# TUTUPA_V2_5sch.net
KiCad netlist of a schematic drawn in EAGLE
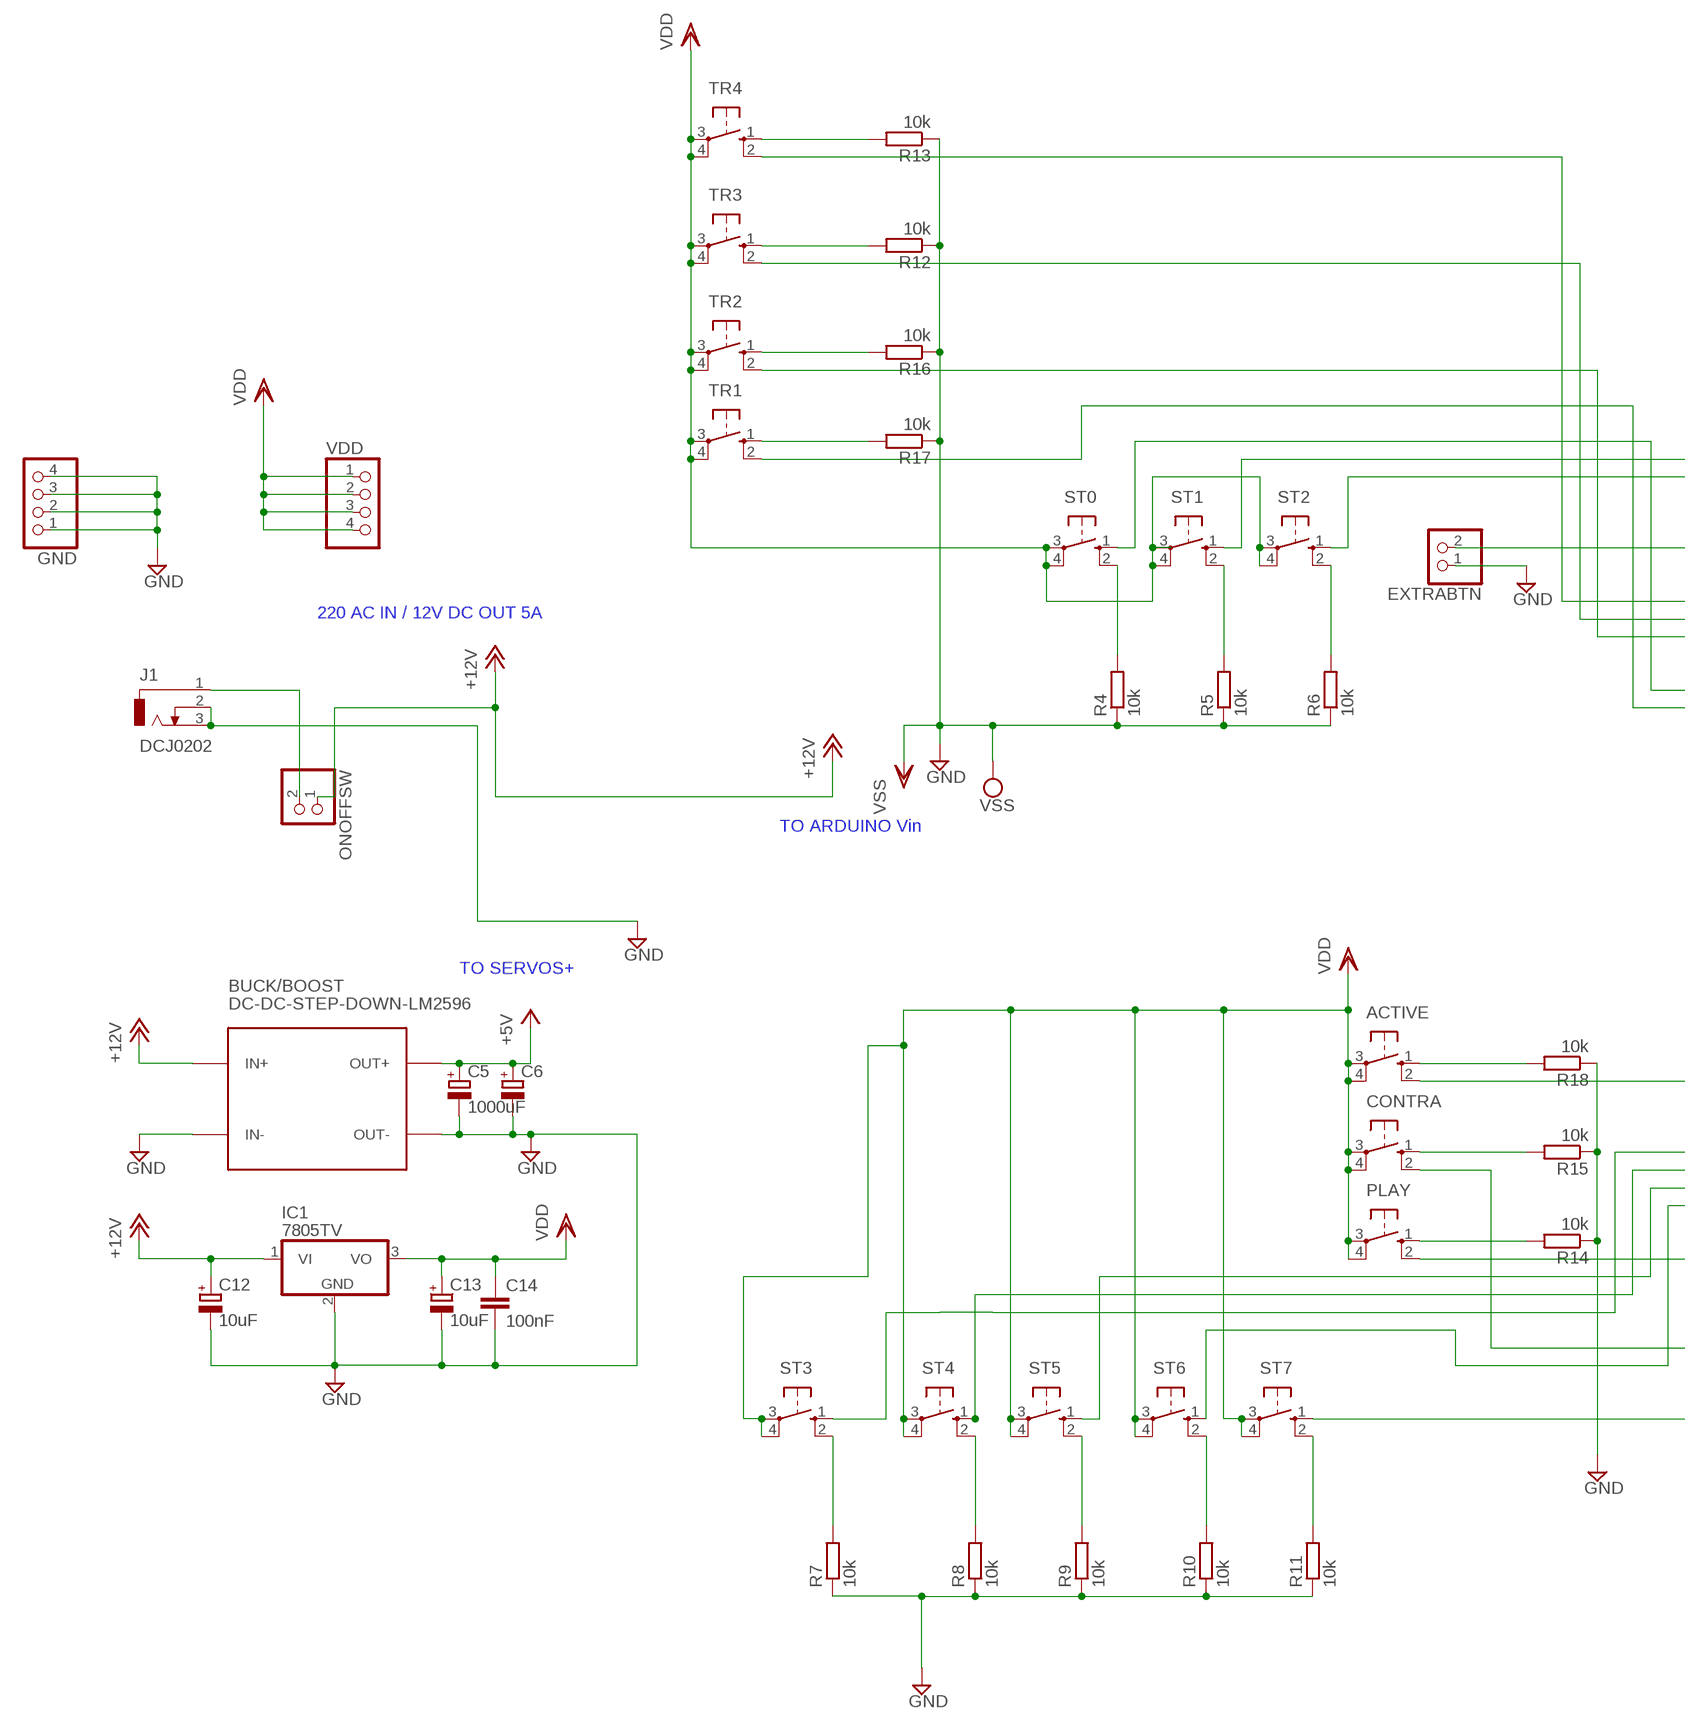
[diagram p0: schematic, sheet 1, part 1 of 2]
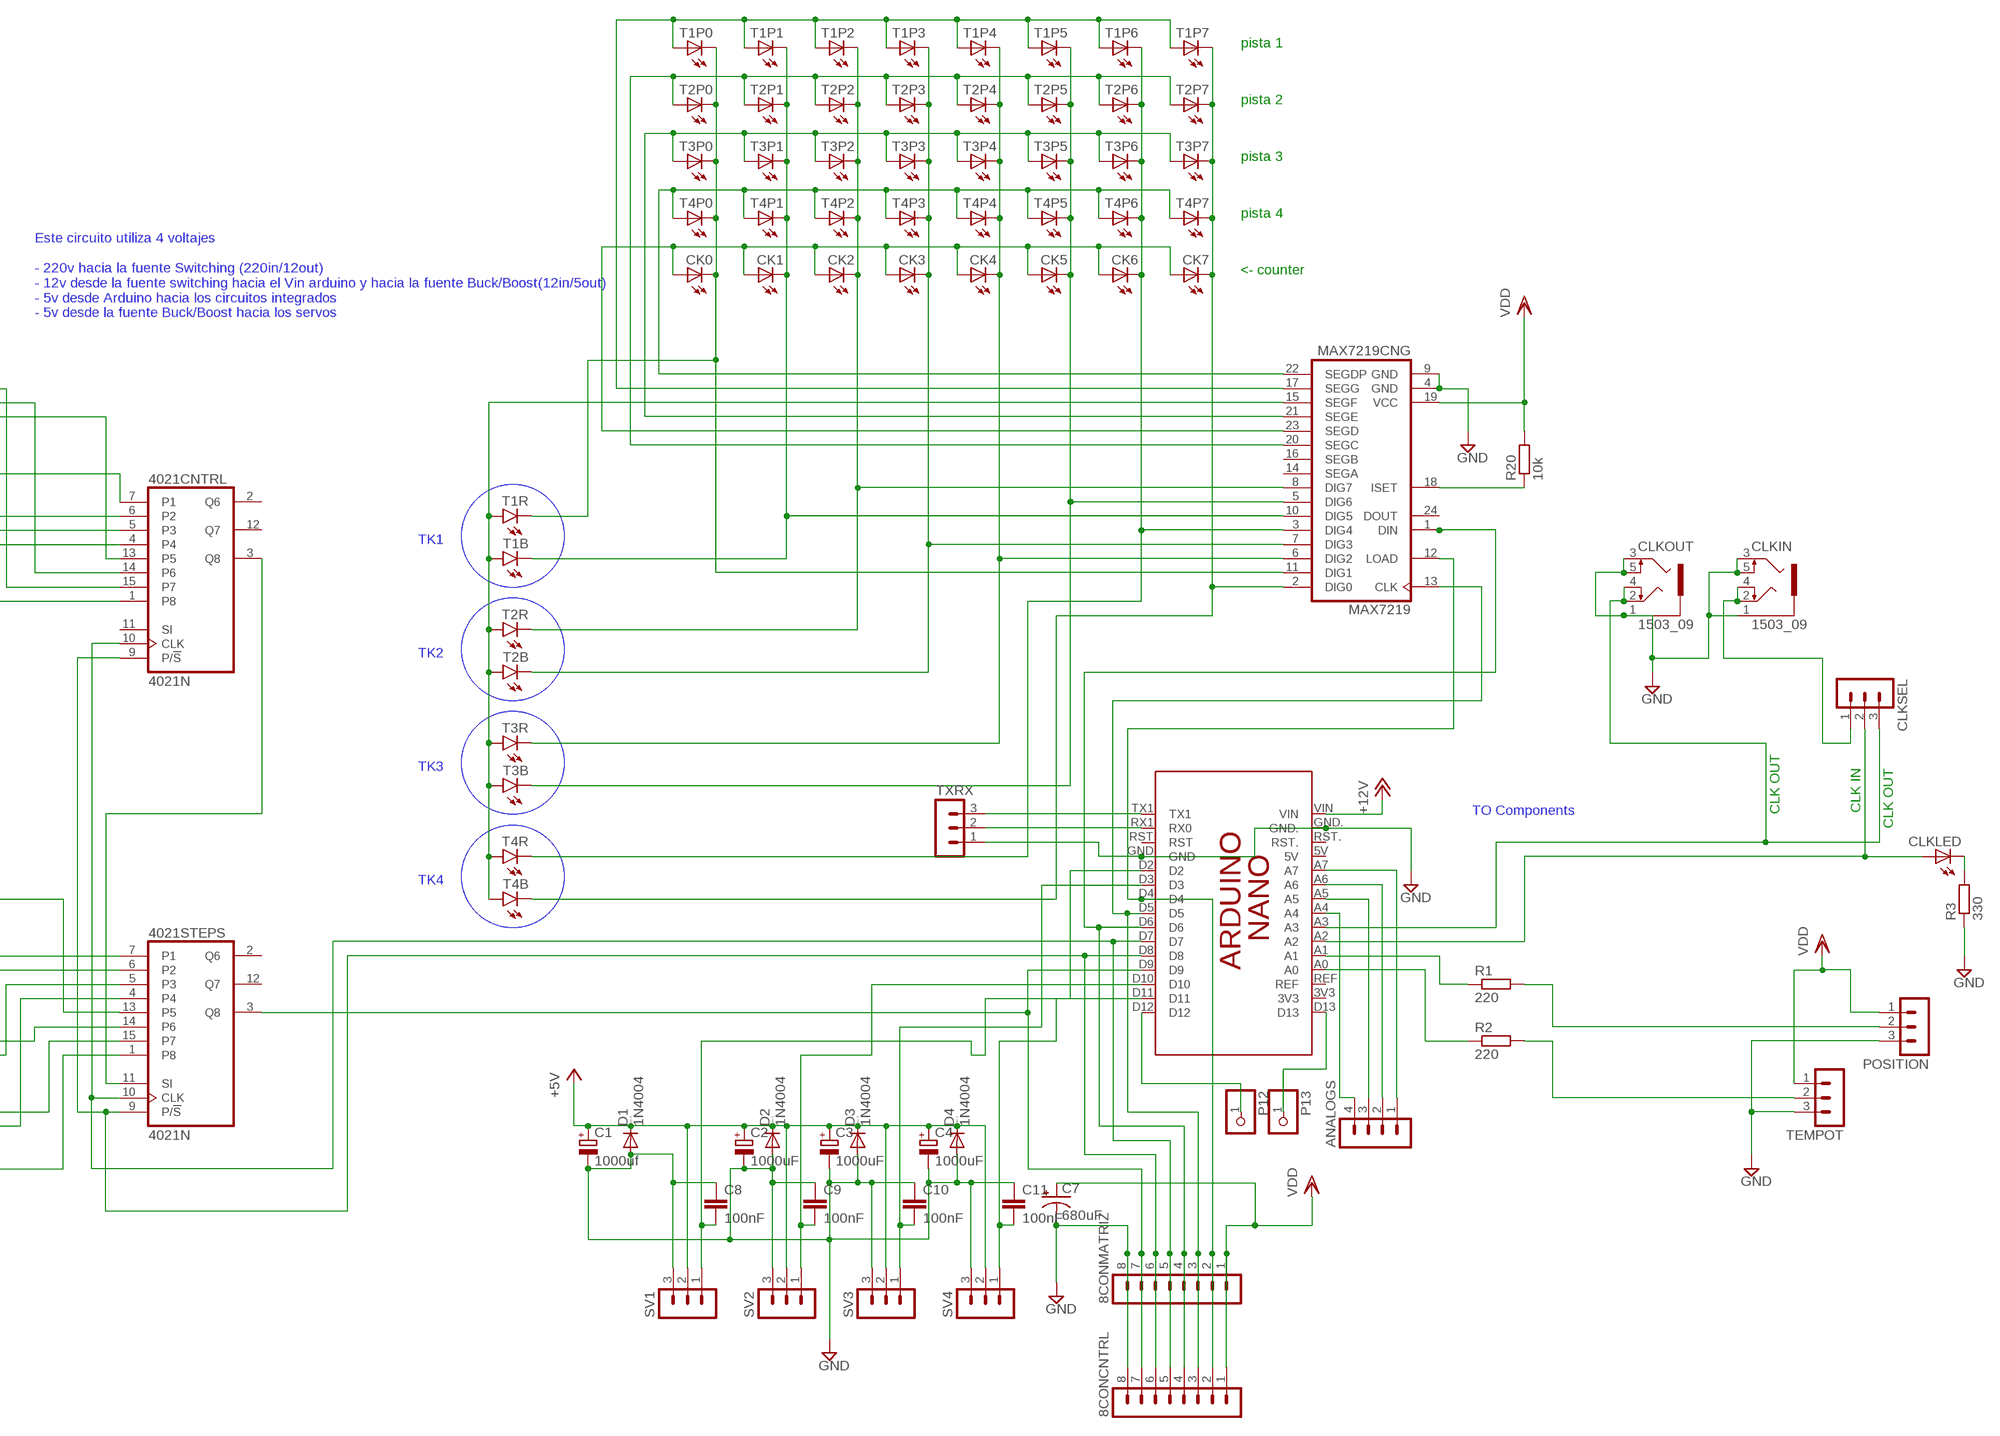
[diagram p1: schematic, sheet 1, part 2 of 2]

(export (version "E")
  (design (tool "Eeschema 10.0.6"))
  (components
    (comp (ref "8CONCNTRL")
      (value "MA08-1W")
      (footprint "eagle-import:MA08-1W")
      (libsource (lib "eagle-import") (part "MA08-1W"))
    )
    (comp (ref "8CONMATRIZ")
      (value "MA08-1W")
      (footprint "eagle-import:MA08-1W")
      (libsource (lib "eagle-import") (part "MA08-1W"))
    )
    (comp (ref "4021CNTRL")
      (value "4021N")
      (footprint "eagle-import:DIL16")
      (libsource (lib "eagle-import") (part "4021N"))
    )
    (comp (ref "4021STEPS")
      (value "4021N")
      (footprint "eagle-import:DIL16")
      (libsource (lib "eagle-import") (part "4021N"))
    )
    (comp (ref "ACTIVE")
      (value "10-XX")
      (footprint "eagle-import:B3F-10XX")
      (fields (field (name "MPN") "B3F-1000"))
      (libsource (lib "eagle-import") (part "10-XX"))
    )
    (comp (ref "ANALOGS")
      (value "MA04-1")
      (footprint "eagle-import:MA04-1")
      (libsource (lib "eagle-import") (part "MA04-1"))
    )
    (comp (ref "BUCK/BOOST")
      (value "DC-DC-STEP-DOWN-LM2596")
      (footprint "eagle-import:DC-DC-STEP-DOWN-LM2596")
      (libsource (lib "eagle-import") (part "DC-DC-STEP-DOWN-LM2596"))
    )
    (comp (ref "C1")
      (value "1000uf")
      (footprint "eagle-import:E5-13")
      (libsource (lib "eagle-import") (part "CPOL-EUE5-13"))
    )
    (comp (ref "C2")
      (value "1000uF")
      (footprint "eagle-import:E5-13")
      (libsource (lib "eagle-import") (part "CPOL-EUE5-13"))
    )
    (comp (ref "C3")
      (value "1000uF")
      (footprint "eagle-import:E5-13")
      (libsource (lib "eagle-import") (part "CPOL-EUE5-13"))
    )
    (comp (ref "C4")
      (value "1000uF")
      (footprint "eagle-import:E5-13")
      (libsource (lib "eagle-import") (part "CPOL-EUE5-13"))
    )
    (comp (ref "C5")
      (value "1000uF")
      (footprint "eagle-import:E5-13")
      (libsource (lib "eagle-import") (part "CPOL-EUE5-13"))
    )
    (comp (ref "C6")
      (value "CPOL-EUE2.5-6")
      (footprint "eagle-import:E2,5-6")
      (libsource (lib "eagle-import") (part "CPOL-EUE2.5-6"))
    )
    (comp (ref "C7")
      (value "680uF")
      (footprint "eagle-import:E5-10,5")
      (libsource (lib "eagle-import") (part "CPOL-USE5-10.5"))
    )
    (comp (ref "C8")
      (value "100nF")
      (footprint "eagle-import:C050-024X044")
      (libsource (lib "eagle-import") (part "C-EU050-024X044"))
    )
    (comp (ref "C9")
      (value "100nF")
      (footprint "eagle-import:C050-024X044")
      (libsource (lib "eagle-import") (part "C-EU050-024X044"))
    )
    (comp (ref "C10")
      (value "100nF")
      (footprint "eagle-import:C050-024X044")
      (libsource (lib "eagle-import") (part "C-EU050-024X044"))
    )
    (comp (ref "C11")
      (value "100nF")
      (footprint "eagle-import:C050-024X044")
      (libsource (lib "eagle-import") (part "C-EU050-024X044"))
    )
    (comp (ref "C12")
      (value "10uF")
      (footprint "eagle-import:E1,8-4")
      (libsource (lib "eagle-import") (part "CPOL-EUE1.8-4"))
    )
    (comp (ref "C13")
      (value "10uF")
      (footprint "eagle-import:E1,8-4")
      (libsource (lib "eagle-import") (part "CPOL-EUE1.8-4"))
    )
    (comp (ref "C14")
      (value "100nF")
      (footprint "eagle-import:C050-024X044")
      (libsource (lib "eagle-import") (part "C-EU050-024X044"))
    )
    (comp (ref "CK0")
      (value "LED5MM")
      (footprint "eagle-import:LED5MM")
      (libsource (lib "eagle-import") (part "led_LED5MM"))
    )
    (comp (ref "CK1")
      (value "LED5MM")
      (footprint "eagle-import:LED5MM")
      (libsource (lib "eagle-import") (part "led_LED5MM"))
    )
    (comp (ref "CK2")
      (value "LED5MM")
      (footprint "eagle-import:LED5MM")
      (libsource (lib "eagle-import") (part "led_LED5MM"))
    )
    (comp (ref "CK3")
      (value "LED5MM")
      (footprint "eagle-import:LED5MM")
      (libsource (lib "eagle-import") (part "led_LED5MM"))
    )
    (comp (ref "CK4")
      (value "LED5MM")
      (footprint "eagle-import:LED5MM")
      (libsource (lib "eagle-import") (part "led_LED5MM"))
    )
    (comp (ref "CK5")
      (value "LED5MM")
      (footprint "eagle-import:LED5MM")
      (libsource (lib "eagle-import") (part "led_LED5MM"))
    )
    (comp (ref "CK6")
      (value "LED5MM")
      (footprint "eagle-import:LED5MM")
      (libsource (lib "eagle-import") (part "led_LED5MM"))
    )
    (comp (ref "CK7")
      (value "LED5MM")
      (footprint "eagle-import:LED5MM")
      (libsource (lib "eagle-import") (part "led_LED5MM"))
    )
    (comp (ref "CLKIN")
      (value "1503_09")
      (footprint "eagle-import:1503_09")
      (libsource (lib "eagle-import") (part "1503_09"))
    )
    (comp (ref "CLKLED")
      (value "LED5MM")
      (footprint "eagle-import:LED5MM")
      (libsource (lib "eagle-import") (part "led_LED5MM"))
    )
    (comp (ref "CLKOUT")
      (value "1503_09")
      (footprint "eagle-import:1503_09")
      (libsource (lib "eagle-import") (part "1503_09"))
    )
    (comp (ref "CLKSEL")
      (value "MA03-1")
      (footprint "eagle-import:MA03-1")
      (libsource (lib "eagle-import") (part "MA03-1"))
    )
    (comp (ref "CONTRA")
      (value "10-XX")
      (footprint "eagle-import:B3F-10XX")
      (fields (field (name "MPN") "B3F-1000"))
      (libsource (lib "eagle-import") (part "10-XX"))
    )
    (comp (ref "D1")
      (value "1N4004")
      (footprint "eagle-import:DO41-10")
      (libsource (lib "eagle-import") (part "1N4004"))
    )
    (comp (ref "D2")
      (value "1N4004")
      (footprint "eagle-import:DO41-10")
      (libsource (lib "eagle-import") (part "1N4004"))
    )
    (comp (ref "D3")
      (value "1N4004")
      (footprint "eagle-import:DO41-10")
      (libsource (lib "eagle-import") (part "1N4004"))
    )
    (comp (ref "D4")
      (value "1N4004")
      (footprint "eagle-import:DO41-10")
      (libsource (lib "eagle-import") (part "1N4004"))
    )
    (comp (ref "EXTRABTN")
      (value "PINHD-1X2")
      (footprint "eagle-import:1X02")
      (libsource (lib "eagle-import") (part "PINHD-1X2"))
    )
    (comp (ref "GND")
      (value "PINHD-1X4")
      (footprint "eagle-import:1X04")
      (libsource (lib "eagle-import") (part "PINHD-1X4"))
    )
    (comp (ref "IC1")
      (value "7805TV")
      (footprint "eagle-import:TO220V")
      (libsource (lib "eagle-import") (part "78TV05"))
    )
    (comp (ref "J1")
      (value "DCJ0202")
      (footprint "eagle-import:DCJ0202")
      (libsource (lib "eagle-import") (part "DCJ0202"))
    )
    (comp (ref "MAX7219")
      (value "MAX7219CNG")
      (footprint "eagle-import:DIL24-3")
      (fields (field (name "MF") "MAXIM"))
      (libsource (lib "eagle-import") (part "MAX7219CNG"))
    )
    (comp (ref "ONOFFSW")
      (value "PINHD-1X2")
      (footprint "eagle-import:1X02")
      (libsource (lib "eagle-import") (part "PINHD-1X2"))
    )
    (comp (ref "P12")
      (value "PINHD-1X1")
      (footprint "eagle-import:1X01")
      (libsource (lib "eagle-import") (part "PINHD-1X1"))
    )
    (comp (ref "P13")
      (value "PINHD-1X1")
      (footprint "eagle-import:1X01")
      (libsource (lib "eagle-import") (part "PINHD-1X1"))
    )
    (comp (ref "PCB1")
      (value "ARDUINO_NANO")
      (footprint "eagle-import:ARDUINO_NANO")
      (libsource (lib "eagle-import") (part "ARDUINO_NANO"))
    )
    (comp (ref "PLAY")
      (value "10-XX")
      (footprint "eagle-import:B3F-10XX")
      (fields (field (name "MPN") "B3F-1000"))
      (libsource (lib "eagle-import") (part "10-XX"))
    )
    (comp (ref "POSITION")
      (value "MA03-1")
      (footprint "eagle-import:MA03-1")
      (libsource (lib "eagle-import") (part "MA03-1"))
    )
    (comp (ref "R1")
      (value "220")
      (footprint "eagle-import:0204_7")
      (libsource (lib "eagle-import") (part "R-EU_0204/7"))
    )
    (comp (ref "R2")
      (value "220")
      (footprint "eagle-import:0204_7")
      (libsource (lib "eagle-import") (part "R-EU_0204/7"))
    )
    (comp (ref "R3")
      (value "330")
      (footprint "eagle-import:0204_7")
      (libsource (lib "eagle-import") (part "R-EU_0204/7"))
    )
    (comp (ref "R4")
      (value "10k")
      (footprint "eagle-import:0207_10")
      (libsource (lib "eagle-import") (part "R-EU_0207/10"))
    )
    (comp (ref "R5")
      (value "10k")
      (footprint "eagle-import:0207_10")
      (libsource (lib "eagle-import") (part "R-EU_0207/10"))
    )
    (comp (ref "R6")
      (value "10k")
      (footprint "eagle-import:0207_10")
      (libsource (lib "eagle-import") (part "R-EU_0207/10"))
    )
    (comp (ref "R7")
      (value "10k")
      (footprint "eagle-import:0207_10")
      (libsource (lib "eagle-import") (part "R-EU_0207/10"))
    )
    (comp (ref "R8")
      (value "10k")
      (footprint "eagle-import:0207_10")
      (libsource (lib "eagle-import") (part "R-EU_0207/10"))
    )
    (comp (ref "R9")
      (value "10k")
      (footprint "eagle-import:0207_10")
      (libsource (lib "eagle-import") (part "R-EU_0207/10"))
    )
    (comp (ref "R10")
      (value "10k")
      (footprint "eagle-import:0207_10")
      (libsource (lib "eagle-import") (part "R-EU_0207/10"))
    )
    (comp (ref "R11")
      (value "10k")
      (footprint "eagle-import:0207_10")
      (libsource (lib "eagle-import") (part "R-EU_0207/10"))
    )
    (comp (ref "R12")
      (value "10k")
      (footprint "eagle-import:0207_10")
      (libsource (lib "eagle-import") (part "R-EU_0207/10"))
    )
    (comp (ref "R13")
      (value "10k")
      (footprint "eagle-import:0207_10")
      (libsource (lib "eagle-import") (part "R-EU_0207/10"))
    )
    (comp (ref "R14")
      (value "10k")
      (footprint "eagle-import:0207_10")
      (libsource (lib "eagle-import") (part "R-EU_0207/10"))
    )
    (comp (ref "R15")
      (value "10k")
      (footprint "eagle-import:0207_10")
      (libsource (lib "eagle-import") (part "R-EU_0207/10"))
    )
    (comp (ref "R16")
      (value "10k")
      (footprint "eagle-import:0207_10")
      (libsource (lib "eagle-import") (part "R-EU_0207/10"))
    )
    (comp (ref "R17")
      (value "10k")
      (footprint "eagle-import:0207_10")
      (libsource (lib "eagle-import") (part "R-EU_0207/10"))
    )
    (comp (ref "R18")
      (value "10k")
      (footprint "eagle-import:0207_10")
      (libsource (lib "eagle-import") (part "R-EU_0207/10"))
    )
    (comp (ref "R20")
      (value "10k")
      (footprint "eagle-import:0207_10")
      (libsource (lib "eagle-import") (part "R-EU_0207/10"))
    )
    (comp (ref "ST0")
      (value "10-XX")
      (footprint "eagle-import:B3F-10XX")
      (fields (field (name "MPN") "B3F-1000"))
      (libsource (lib "eagle-import") (part "10-XX"))
    )
    (comp (ref "ST1")
      (value "10-XX")
      (footprint "eagle-import:B3F-10XX")
      (fields (field (name "MPN") "B3F-1000"))
      (libsource (lib "eagle-import") (part "10-XX"))
    )
    (comp (ref "ST2")
      (value "10-XX")
      (footprint "eagle-import:B3F-10XX")
      (fields (field (name "MPN") "B3F-1000"))
      (libsource (lib "eagle-import") (part "10-XX"))
    )
    (comp (ref "ST3")
      (value "10-XX")
      (footprint "eagle-import:B3F-10XX")
      (fields (field (name "MPN") "B3F-1000"))
      (libsource (lib "eagle-import") (part "10-XX"))
    )
    (comp (ref "ST4")
      (value "10-XX")
      (footprint "eagle-import:B3F-10XX")
      (fields (field (name "MPN") "B3F-1000"))
      (libsource (lib "eagle-import") (part "10-XX"))
    )
    (comp (ref "ST5")
      (value "10-XX")
      (footprint "eagle-import:B3F-10XX")
      (fields (field (name "MPN") "B3F-1000"))
      (libsource (lib "eagle-import") (part "10-XX"))
    )
    (comp (ref "ST6")
      (value "10-XX")
      (footprint "eagle-import:B3F-10XX")
      (fields (field (name "MPN") "B3F-1000"))
      (libsource (lib "eagle-import") (part "10-XX"))
    )
    (comp (ref "ST7")
      (value "10-XX")
      (footprint "eagle-import:B3F-10XX")
      (fields (field (name "MPN") "B3F-1000"))
      (libsource (lib "eagle-import") (part "10-XX"))
    )
    (comp (ref "SV1")
      (value "MA03-1")
      (footprint "eagle-import:MA03-1")
      (libsource (lib "eagle-import") (part "MA03-1"))
    )
    (comp (ref "SV2")
      (value "MA03-1")
      (footprint "eagle-import:MA03-1")
      (libsource (lib "eagle-import") (part "MA03-1"))
    )
    (comp (ref "SV3")
      (value "MA03-1")
      (footprint "eagle-import:MA03-1")
      (libsource (lib "eagle-import") (part "MA03-1"))
    )
    (comp (ref "SV4")
      (value "MA03-1")
      (footprint "eagle-import:MA03-1")
      (libsource (lib "eagle-import") (part "MA03-1"))
    )
    (comp (ref "T1B")
      (value "LED3MM")
      (footprint "eagle-import:LED3MM")
      (libsource (lib "eagle-import") (part "LED3MM"))
    )
    (comp (ref "T1P0")
      (value "LED5MM")
      (footprint "eagle-import:LED5MM")
      (libsource (lib "eagle-import") (part "led_LED5MM"))
    )
    (comp (ref "T1P1")
      (value "LED5MM")
      (footprint "eagle-import:LED5MM")
      (libsource (lib "eagle-import") (part "led_LED5MM"))
    )
    (comp (ref "T1P2")
      (value "LED5MM")
      (footprint "eagle-import:LED5MM")
      (libsource (lib "eagle-import") (part "led_LED5MM"))
    )
    (comp (ref "T1P3")
      (value "LED5MM")
      (footprint "eagle-import:LED5MM")
      (libsource (lib "eagle-import") (part "led_LED5MM"))
    )
    (comp (ref "T1P4")
      (value "LED5MM")
      (footprint "eagle-import:LED5MM")
      (libsource (lib "eagle-import") (part "led_LED5MM"))
    )
    (comp (ref "T1P5")
      (value "LED5MM")
      (footprint "eagle-import:LED5MM")
      (libsource (lib "eagle-import") (part "led_LED5MM"))
    )
    (comp (ref "T1P6")
      (value "LED5MM")
      (footprint "eagle-import:LED5MM")
      (libsource (lib "eagle-import") (part "led_LED5MM"))
    )
    (comp (ref "T1P7")
      (value "LED5MM")
      (footprint "eagle-import:LED5MM")
      (libsource (lib "eagle-import") (part "led_LED5MM"))
    )
    (comp (ref "T1R")
      (value "LED3MM")
      (footprint "eagle-import:LED3MM")
      (libsource (lib "eagle-import") (part "LED3MM"))
    )
    (comp (ref "T2B")
      (value "LED3MM")
      (footprint "eagle-import:LED3MM")
      (libsource (lib "eagle-import") (part "LED3MM"))
    )
    (comp (ref "T2P0")
      (value "LED5MM")
      (footprint "eagle-import:LED5MM")
      (libsource (lib "eagle-import") (part "led_LED5MM"))
    )
    (comp (ref "T2P1")
      (value "LED5MM")
      (footprint "eagle-import:LED5MM")
      (libsource (lib "eagle-import") (part "led_LED5MM"))
    )
    (comp (ref "T2P2")
      (value "LED5MM")
      (footprint "eagle-import:LED5MM")
      (libsource (lib "eagle-import") (part "led_LED5MM"))
    )
    (comp (ref "T2P3")
      (value "LED5MM")
      (footprint "eagle-import:LED5MM")
      (libsource (lib "eagle-import") (part "led_LED5MM"))
    )
    (comp (ref "T2P4")
      (value "LED5MM")
      (footprint "eagle-import:LED5MM")
      (libsource (lib "eagle-import") (part "led_LED5MM"))
    )
    (comp (ref "T2P5")
      (value "LED5MM")
      (footprint "eagle-import:LED5MM")
      (libsource (lib "eagle-import") (part "led_LED5MM"))
    )
    (comp (ref "T2P6")
      (value "LED5MM")
      (footprint "eagle-import:LED5MM")
      (libsource (lib "eagle-import") (part "led_LED5MM"))
    )
    (comp (ref "T2P7")
      (value "LED5MM")
      (footprint "eagle-import:LED5MM")
      (libsource (lib "eagle-import") (part "led_LED5MM"))
    )
    (comp (ref "T2R")
      (value "LED3MM")
      (footprint "eagle-import:LED3MM")
      (libsource (lib "eagle-import") (part "LED3MM"))
    )
    (comp (ref "T3B")
      (value "LED3MM")
      (footprint "eagle-import:LED3MM")
      (libsource (lib "eagle-import") (part "LED3MM"))
    )
    (comp (ref "T3P0")
      (value "LED5MM")
      (footprint "eagle-import:LED5MM")
      (libsource (lib "eagle-import") (part "led_LED5MM"))
    )
    (comp (ref "T3P1")
      (value "LED5MM")
      (footprint "eagle-import:LED5MM")
      (libsource (lib "eagle-import") (part "led_LED5MM"))
    )
    (comp (ref "T3P2")
      (value "LED5MM")
      (footprint "eagle-import:LED5MM")
      (libsource (lib "eagle-import") (part "led_LED5MM"))
    )
    (comp (ref "T3P3")
      (value "LED5MM")
      (footprint "eagle-import:LED5MM")
      (libsource (lib "eagle-import") (part "led_LED5MM"))
    )
    (comp (ref "T3P4")
      (value "LED5MM")
      (footprint "eagle-import:LED5MM")
      (libsource (lib "eagle-import") (part "led_LED5MM"))
    )
    (comp (ref "T3P5")
      (value "LED5MM")
      (footprint "eagle-import:LED5MM")
      (libsource (lib "eagle-import") (part "led_LED5MM"))
    )
    (comp (ref "T3P6")
      (value "LED5MM")
      (footprint "eagle-import:LED5MM")
      (libsource (lib "eagle-import") (part "led_LED5MM"))
    )
    (comp (ref "T3P7")
      (value "LED5MM")
      (footprint "eagle-import:LED5MM")
      (libsource (lib "eagle-import") (part "led_LED5MM"))
    )
    (comp (ref "T3R")
      (value "LED3MM")
      (footprint "eagle-import:LED3MM")
      (libsource (lib "eagle-import") (part "LED3MM"))
    )
    (comp (ref "T4B")
      (value "LED3MM")
      (footprint "eagle-import:LED3MM")
      (libsource (lib "eagle-import") (part "LED3MM"))
    )
    (comp (ref "T4P0")
      (value "LED5MM")
      (footprint "eagle-import:LED5MM")
      (libsource (lib "eagle-import") (part "led_LED5MM"))
    )
    (comp (ref "T4P1")
      (value "LED5MM")
      (footprint "eagle-import:LED5MM")
      (libsource (lib "eagle-import") (part "led_LED5MM"))
    )
    (comp (ref "T4P2")
      (value "LED5MM")
      (footprint "eagle-import:LED5MM")
      (libsource (lib "eagle-import") (part "led_LED5MM"))
    )
    (comp (ref "T4P3")
      (value "LED5MM")
      (footprint "eagle-import:LED5MM")
      (libsource (lib "eagle-import") (part "led_LED5MM"))
    )
    (comp (ref "T4P4")
      (value "LED5MM")
      (footprint "eagle-import:LED5MM")
      (libsource (lib "eagle-import") (part "led_LED5MM"))
    )
    (comp (ref "T4P5")
      (value "LED5MM")
      (footprint "eagle-import:LED5MM")
      (libsource (lib "eagle-import") (part "led_LED5MM"))
    )
    (comp (ref "T4P6")
      (value "LED5MM")
      (footprint "eagle-import:LED5MM")
      (libsource (lib "eagle-import") (part "led_LED5MM"))
    )
    (comp (ref "T4P7")
      (value "LED5MM")
      (footprint "eagle-import:LED5MM")
      (libsource (lib "eagle-import") (part "led_LED5MM"))
    )
    (comp (ref "T4R")
      (value "LED3MM")
      (footprint "eagle-import:LED3MM")
      (libsource (lib "eagle-import") (part "LED3MM"))
    )
    (comp (ref "TEMPOT")
      (value "MA03-1")
      (footprint "eagle-import:MA03-1")
      (libsource (lib "eagle-import") (part "MA03-1"))
    )
    (comp (ref "TR1")
      (value "10-XX")
      (footprint "eagle-import:B3F-10XX")
      (fields (field (name "MPN") "B3F-1000"))
      (libsource (lib "eagle-import") (part "10-XX"))
    )
    (comp (ref "TR2")
      (value "10-XX")
      (footprint "eagle-import:B3F-10XX")
      (fields (field (name "MPN") "B3F-1000"))
      (libsource (lib "eagle-import") (part "10-XX"))
    )
    (comp (ref "TR3")
      (value "10-XX")
      (footprint "eagle-import:B3F-10XX")
      (fields (field (name "MPN") "B3F-1000"))
      (libsource (lib "eagle-import") (part "10-XX"))
    )
    (comp (ref "TR4")
      (value "10-XX")
      (footprint "eagle-import:B3F-10XX")
      (fields (field (name "MPN") "B3F-1000"))
      (libsource (lib "eagle-import") (part "10-XX"))
    )
    (comp (ref "TXRX")
      (value "MA03-1")
      (footprint "eagle-import:MA03-1")
      (libsource (lib "eagle-import") (part "MA03-1"))
    )
    (comp (ref "VDD")
      (value "PINHD-1X4")
      (footprint "eagle-import:1X04")
      (libsource (lib "eagle-import") (part "PINHD-1X4"))
    )
  )
  (nets
    (net (code "1") (name "+5V") (class "Default")
      (node (ref "BUCK/BOOST") (pin "OUT+") (pinfunction "OUT+_OUT+") (pintype "bidirectional"))
      (node (ref "C1") (pin "+") (pinfunction "+_+") (pintype "passive"))
      (node (ref "C2") (pin "+") (pinfunction "+_+") (pintype "passive"))
      (node (ref "C3") (pin "+") (pinfunction "+_+") (pintype "passive"))
      (node (ref "C4") (pin "+") (pinfunction "+_+") (pintype "passive"))
      (node (ref "C5") (pin "+") (pinfunction "+_+") (pintype "passive"))
      (node (ref "C6") (pin "+") (pinfunction "+_+") (pintype "passive"))
      (node (ref "D1") (pin "C") (pinfunction "C_C") (pintype "passive"))
      (node (ref "D2") (pin "C") (pinfunction "C_C") (pintype "passive"))
      (node (ref "D3") (pin "C") (pinfunction "C_C") (pintype "passive"))
      (node (ref "D4") (pin "C") (pinfunction "C_C") (pintype "passive"))
      (node (ref "SV1") (pin "2") (pinfunction "2_2") (pintype "passive"))
      (node (ref "SV2") (pin "2") (pinfunction "2_2") (pintype "passive"))
      (node (ref "SV3") (pin "2") (pinfunction "2_2") (pintype "passive"))
      (node (ref "SV4") (pin "2") (pinfunction "2_2") (pintype "passive"))
    )
    (net (code "2") (name "+12V") (class "Default")
      (node (ref "BUCK/BOOST") (pin "IN+") (pinfunction "IN+_IN+") (pintype "bidirectional"))
      (node (ref "C12") (pin "+") (pinfunction "+_+") (pintype "passive"))
      (node (ref "IC1") (pin "1") (pinfunction "VI_1") (pintype "input"))
      (node (ref "ONOFFSW") (pin "1") (pinfunction "1_1") (pintype "passive"))
      (node (ref "PCB1") (pin "VIN") (pinfunction "VIN_VIN") (pintype "bidirectional"))
    )
    (net (code "3") (name "GND") (class "Default")
      (node (ref "8CONCNTRL") (pin "8") (pinfunction "8_8") (pintype "passive"))
      (node (ref "8CONMATRIZ") (pin "8") (pinfunction "8_8") (pintype "passive"))
      (node (ref "BUCK/BOOST") (pin "IN-") (pinfunction "IN-_IN-") (pintype "bidirectional"))
      (node (ref "BUCK/BOOST") (pin "OUT-") (pinfunction "OUT-_OUT-") (pintype "bidirectional"))
      (node (ref "C1") (pin "-") (pinfunction "-_-") (pintype "passive"))
      (node (ref "C10") (pin "1") (pinfunction "1_1") (pintype "passive"))
      (node (ref "C11") (pin "1") (pinfunction "1_1") (pintype "passive"))
      (node (ref "C12") (pin "-") (pinfunction "-_-") (pintype "passive"))
      (node (ref "C13") (pin "-") (pinfunction "-_-") (pintype "passive"))
      (node (ref "C14") (pin "2") (pinfunction "2_2") (pintype "passive"))
      (node (ref "C2") (pin "-") (pinfunction "-_-") (pintype "passive"))
      (node (ref "C3") (pin "-") (pinfunction "-_-") (pintype "passive"))
      (node (ref "C4") (pin "-") (pinfunction "-_-") (pintype "passive"))
      (node (ref "C5") (pin "-") (pinfunction "-_-") (pintype "passive"))
      (node (ref "C6") (pin "-") (pinfunction "-_-") (pintype "passive"))
      (node (ref "C7") (pin "-") (pinfunction "-_-") (pintype "passive"))
      (node (ref "C8") (pin "1") (pinfunction "1_1") (pintype "passive"))
      (node (ref "C9") (pin "1") (pinfunction "1_1") (pintype "passive"))
      (node (ref "CLKIN") (pin "1") (pinfunction "1_1") (pintype "passive"))
      (node (ref "CLKIN") (pin "3") (pinfunction "3_3") (pintype "passive"))
      (node (ref "CLKIN") (pin "5") (pinfunction "5_5") (pintype "passive"))
      (node (ref "CLKOUT") (pin "1") (pinfunction "1_1") (pintype "passive"))
      (node (ref "CLKOUT") (pin "3") (pinfunction "3_3") (pintype "passive"))
      (node (ref "CLKOUT") (pin "5") (pinfunction "5_5") (pintype "passive"))
      (node (ref "D1") (pin "A") (pinfunction "A_A") (pintype "passive"))
      (node (ref "D2") (pin "A") (pinfunction "A_A") (pintype "passive"))
      (node (ref "D3") (pin "A") (pinfunction "A_A") (pintype "passive"))
      (node (ref "D4") (pin "A") (pinfunction "A_A") (pintype "passive"))
      (node (ref "EXTRABTN") (pin "1") (pinfunction "1_1") (pintype "passive"))
      (node (ref "GND") (pin "1") (pinfunction "1_1") (pintype "passive"))
      (node (ref "GND") (pin "2") (pinfunction "2_2") (pintype "passive"))
      (node (ref "GND") (pin "3") (pinfunction "3_3") (pintype "passive"))
      (node (ref "GND") (pin "4") (pinfunction "4_4") (pintype "passive"))
      (node (ref "IC1") (pin "2") (pinfunction "GND_2") (pintype "passive"))
      (node (ref "J1") (pin "2") (pinfunction "2_2") (pintype "passive"))
      (node (ref "J1") (pin "3") (pinfunction "3_3") (pintype "passive"))
      (node (ref "MAX7219") (pin "4") (pinfunction "GND_4") (pintype "power_in"))
      (node (ref "MAX7219") (pin "9") (pinfunction "GND_9") (pintype "power_in"))
      (node (ref "PCB1") (pin "GND") (pinfunction "GND_GND") (pintype "bidirectional"))
      (node (ref "PCB1") (pin "GND.") (pinfunction "GND._GND.") (pintype "bidirectional"))
      (node (ref "POSITION") (pin "3") (pinfunction "3_3") (pintype "passive"))
      (node (ref "R10") (pin "1") (pinfunction "1_1") (pintype "passive"))
      (node (ref "R11") (pin "1") (pinfunction "1_1") (pintype "passive"))
      (node (ref "R12") (pin "1") (pinfunction "1_1") (pintype "passive"))
      (node (ref "R13") (pin "1") (pinfunction "1_1") (pintype "passive"))
      (node (ref "R14") (pin "1") (pinfunction "1_1") (pintype "passive"))
      (node (ref "R15") (pin "1") (pinfunction "1_1") (pintype "passive"))
      (node (ref "R16") (pin "1") (pinfunction "1_1") (pintype "passive"))
      (node (ref "R17") (pin "1") (pinfunction "1_1") (pintype "passive"))
      (node (ref "R18") (pin "1") (pinfunction "1_1") (pintype "passive"))
      (node (ref "R3") (pin "1") (pinfunction "1_1") (pintype "passive"))
      (node (ref "R4") (pin "1") (pinfunction "1_1") (pintype "passive"))
      (node (ref "R5") (pin "1") (pinfunction "1_1") (pintype "passive"))
      (node (ref "R6") (pin "1") (pinfunction "1_1") (pintype "passive"))
      (node (ref "R7") (pin "1") (pinfunction "1_1") (pintype "passive"))
      (node (ref "R8") (pin "1") (pinfunction "1_1") (pintype "passive"))
      (node (ref "R9") (pin "1") (pinfunction "1_1") (pintype "passive"))
      (node (ref "SV1") (pin "3") (pinfunction "3_3") (pintype "passive"))
      (node (ref "SV2") (pin "3") (pinfunction "3_3") (pintype "passive"))
      (node (ref "SV3") (pin "3") (pinfunction "3_3") (pintype "passive"))
      (node (ref "SV4") (pin "3") (pinfunction "3_3") (pintype "passive"))
      (node (ref "TEMPOT") (pin "3") (pinfunction "3_3") (pintype "passive"))
      (node (ref "TXRX") (pin "1") (pinfunction "1_1") (pintype "passive"))
    )
    (net (code "4") (name "Net-(4021CNTRLA-CLK)") (class "Default")
      (node (ref "4021CNTRL") (pin "10") (pinfunction "CLK_10") (pintype "input"))
      (node (ref "4021STEPS") (pin "10") (pinfunction "CLK_10") (pintype "input"))
      (node (ref "8CONCNTRL") (pin "5") (pinfunction "5_5") (pintype "passive"))
      (node (ref "8CONMATRIZ") (pin "5") (pinfunction "5_5") (pintype "passive"))
      (node (ref "PCB1") (pin "D7") (pinfunction "D7_D7") (pintype "bidirectional"))
    )
    (net (code "5") (name "Net-(4021CNTRLA-P1)") (class "Default")
      (node (ref "4021CNTRL") (pin "7") (pinfunction "P1_7") (pintype "input"))
      (node (ref "EXTRABTN") (pin "2") (pinfunction "2_2") (pintype "passive"))
    )
    (net (code "6") (name "Net-(4021CNTRLA-P2)") (class "Default")
      (node (ref "4021CNTRL") (pin "6") (pinfunction "P2_6") (pintype "input"))
      (node (ref "TR4") (pin "2") (pinfunction "S1_2") (pintype "passive"))
    )
    (net (code "7") (name "Net-(4021CNTRLA-P3)") (class "Default")
      (node (ref "4021CNTRL") (pin "5") (pinfunction "P3_5") (pintype "input"))
      (node (ref "TR3") (pin "2") (pinfunction "S1_2") (pintype "passive"))
    )
    (net (code "8") (name "Net-(4021CNTRLA-P4)") (class "Default")
      (node (ref "4021CNTRL") (pin "4") (pinfunction "P4_4") (pintype "input"))
      (node (ref "TR2") (pin "2") (pinfunction "S1_2") (pintype "passive"))
    )
    (net (code "9") (name "Net-(4021CNTRLA-P5)") (class "Default")
      (node (ref "4021CNTRL") (pin "13") (pinfunction "P5_13") (pintype "input"))
      (node (ref "ST2") (pin "1") (pinfunction "S_1") (pintype "passive"))
    )
    (net (code "10") (name "Net-(4021CNTRLA-P6)") (class "Default")
      (node (ref "4021CNTRL") (pin "14") (pinfunction "P6_14") (pintype "input"))
      (node (ref "ST1") (pin "1") (pinfunction "S_1") (pintype "passive"))
    )
    (net (code "11") (name "Net-(4021CNTRLA-P7)") (class "Default")
      (node (ref "4021CNTRL") (pin "15") (pinfunction "P7_15") (pintype "input"))
      (node (ref "ST0") (pin "1") (pinfunction "S_1") (pintype "passive"))
    )
    (net (code "12") (name "Net-(4021CNTRLA-P8)") (class "Default")
      (node (ref "4021CNTRL") (pin "1") (pinfunction "P8_1") (pintype "input"))
      (node (ref "TR1") (pin "2") (pinfunction "S1_2") (pintype "passive"))
    )
    (net (code "13") (name "Net-(4021CNTRLA-P{slash}~{S})") (class "Default")
      (node (ref "4021CNTRL") (pin "9") (pinfunction "P/~{S}_9") (pintype "input"))
      (node (ref "4021STEPS") (pin "9") (pinfunction "P/~{S}_9") (pintype "input"))
      (node (ref "8CONCNTRL") (pin "6") (pinfunction "6_6") (pintype "passive"))
      (node (ref "8CONMATRIZ") (pin "6") (pinfunction "6_6") (pintype "passive"))
      (node (ref "PCB1") (pin "D8") (pinfunction "D8_D8") (pintype "bidirectional"))
    )
    (net (code "14") (name "Net-(4021CNTRLA-Q8)") (class "Default")
      (node (ref "4021CNTRL") (pin "3") (pinfunction "Q8_3") (pintype "output"))
      (node (ref "4021STEPS") (pin "11") (pinfunction "SI_11") (pintype "input"))
    )
    (net (code "15") (name "Net-(4021STEPSA-P1)") (class "Default")
      (node (ref "4021STEPS") (pin "7") (pinfunction "P1_7") (pintype "input"))
      (node (ref "ST3") (pin "1") (pinfunction "S_1") (pintype "passive"))
    )
    (net (code "16") (name "Net-(4021STEPSA-P2)") (class "Default")
      (node (ref "4021STEPS") (pin "6") (pinfunction "P2_6") (pintype "input"))
      (node (ref "ST4") (pin "1") (pinfunction "S_1") (pintype "passive"))
    )
    (net (code "17") (name "Net-(4021STEPSA-P3)") (class "Default")
      (node (ref "4021STEPS") (pin "5") (pinfunction "P3_5") (pintype "input"))
      (node (ref "ST5") (pin "1") (pinfunction "S_1") (pintype "passive"))
    )
    (net (code "18") (name "Net-(4021STEPSA-P4)") (class "Default")
      (node (ref "4021STEPS") (pin "4") (pinfunction "P4_4") (pintype "input"))
      (node (ref "ST6") (pin "1") (pinfunction "S_1") (pintype "passive"))
    )
    (net (code "19") (name "Net-(4021STEPSA-P5)") (class "Default")
      (node (ref "4021STEPS") (pin "13") (pinfunction "P5_13") (pintype "input"))
      (node (ref "ACTIVE") (pin "2") (pinfunction "S1_2") (pintype "passive"))
    )
    (net (code "20") (name "Net-(4021STEPSA-P6)") (class "Default")
      (node (ref "4021STEPS") (pin "14") (pinfunction "P6_14") (pintype "input"))
      (node (ref "PLAY") (pin "2") (pinfunction "S1_2") (pintype "passive"))
    )
    (net (code "21") (name "Net-(4021STEPSA-P7)") (class "Default")
      (node (ref "4021STEPS") (pin "15") (pinfunction "P7_15") (pintype "input"))
      (node (ref "CONTRA") (pin "2") (pinfunction "S1_2") (pintype "passive"))
    )
    (net (code "22") (name "Net-(4021STEPSA-P8)") (class "Default")
      (node (ref "4021STEPS") (pin "1") (pinfunction "P8_1") (pintype "input"))
      (node (ref "ST7") (pin "1") (pinfunction "S_1") (pintype "passive"))
    )
    (net (code "23") (name "Net-(4021STEPSA-Q8)") (class "Default")
      (node (ref "4021STEPS") (pin "3") (pinfunction "Q8_3") (pintype "output"))
      (node (ref "8CONCNTRL") (pin "7") (pinfunction "7_7") (pintype "passive"))
      (node (ref "8CONMATRIZ") (pin "7") (pinfunction "7_7") (pintype "passive"))
      (node (ref "PCB1") (pin "D9") (pinfunction "D9_D9") (pintype "bidirectional"))
    )
    (net (code "24") (name "Net-(ACTIVE-S)") (class "Default")
      (node (ref "ACTIVE") (pin "1") (pinfunction "S_1") (pintype "passive"))
      (node (ref "R18") (pin "2") (pinfunction "2_2") (pintype "passive"))
    )
    (net (code "25") (name "Net-(ANALOGS-Pad1)") (class "Default")
      (node (ref "ANALOGS") (pin "1") (pinfunction "1_1") (pintype "passive"))
      (node (ref "PCB1") (pin "A7") (pinfunction "A7_A7") (pintype "bidirectional"))
    )
    (net (code "26") (name "Net-(ANALOGS-Pad2)") (class "Default")
      (node (ref "ANALOGS") (pin "2") (pinfunction "2_2") (pintype "passive"))
      (node (ref "PCB1") (pin "A6") (pinfunction "A6_A6") (pintype "bidirectional"))
    )
    (net (code "27") (name "Net-(ANALOGS-Pad3)") (class "Default")
      (node (ref "ANALOGS") (pin "3") (pinfunction "3_3") (pintype "passive"))
      (node (ref "PCB1") (pin "A5") (pinfunction "A5_A5") (pintype "bidirectional"))
    )
    (net (code "28") (name "Net-(ANALOGS-Pad4)") (class "Default")
      (node (ref "ANALOGS") (pin "4") (pinfunction "4_4") (pintype "passive"))
      (node (ref "PCB1") (pin "A4") (pinfunction "A4_A4") (pintype "bidirectional"))
    )
    (net (code "29") (name "Net-(C8-Pad2)") (class "Default")
      (node (ref "C8") (pin "2") (pinfunction "2_2") (pintype "passive"))
      (node (ref "PCB1") (pin "D11") (pinfunction "D11_D11") (pintype "bidirectional"))
      (node (ref "SV1") (pin "1") (pinfunction "1_1") (pintype "passive"))
    )
    (net (code "30") (name "Net-(C9-Pad2)") (class "Default")
      (node (ref "C9") (pin "2") (pinfunction "2_2") (pintype "passive"))
      (node (ref "PCB1") (pin "D10") (pinfunction "D10_D10") (pintype "bidirectional"))
      (node (ref "SV2") (pin "1") (pinfunction "1_1") (pintype "passive"))
    )
    (net (code "31") (name "Net-(C10-Pad2)") (class "Default")
      (node (ref "C10") (pin "2") (pinfunction "2_2") (pintype "passive"))
      (node (ref "PCB1") (pin "D3") (pinfunction "D3_D3") (pintype "bidirectional"))
      (node (ref "SV3") (pin "1") (pinfunction "1_1") (pintype "passive"))
    )
    (net (code "32") (name "Net-(C11-Pad2)") (class "Default")
      (node (ref "C11") (pin "2") (pinfunction "2_2") (pintype "passive"))
      (node (ref "PCB1") (pin "D2") (pinfunction "D2_D2") (pintype "bidirectional"))
      (node (ref "SV4") (pin "1") (pinfunction "1_1") (pintype "passive"))
    )
    (net (code "33") (name "Net-(CK0-C)") (class "Default")
      (node (ref "CK0") (pin "K") (pinfunction "C_K") (pintype "passive"))
      (node (ref "MAX7219") (pin "11") (pinfunction "DIG1_11") (pintype "output"))
      (node (ref "T1P0") (pin "K") (pinfunction "C_K") (pintype "passive"))
      (node (ref "T1R") (pin "K") (pinfunction "C_K") (pintype "passive"))
      (node (ref "T2P0") (pin "K") (pinfunction "C_K") (pintype "passive"))
      (node (ref "T3P0") (pin "K") (pinfunction "C_K") (pintype "passive"))
      (node (ref "T4P0") (pin "K") (pinfunction "C_K") (pintype "passive"))
    )
    (net (code "34") (name "Net-(CK1-C)") (class "Default")
      (node (ref "CK1") (pin "K") (pinfunction "C_K") (pintype "passive"))
      (node (ref "MAX7219") (pin "10") (pinfunction "DIG5_10") (pintype "output"))
      (node (ref "T1B") (pin "K") (pinfunction "C_K") (pintype "passive"))
      (node (ref "T1P1") (pin "K") (pinfunction "C_K") (pintype "passive"))
      (node (ref "T2P1") (pin "K") (pinfunction "C_K") (pintype "passive"))
      (node (ref "T3P1") (pin "K") (pinfunction "C_K") (pintype "passive"))
      (node (ref "T4P1") (pin "K") (pinfunction "C_K") (pintype "passive"))
    )
    (net (code "35") (name "Net-(CK2-C)") (class "Default")
      (node (ref "CK2") (pin "K") (pinfunction "C_K") (pintype "passive"))
      (node (ref "MAX7219") (pin "8") (pinfunction "DIG7_8") (pintype "output"))
      (node (ref "T1P2") (pin "K") (pinfunction "C_K") (pintype "passive"))
      (node (ref "T2P2") (pin "K") (pinfunction "C_K") (pintype "passive"))
      (node (ref "T2R") (pin "K") (pinfunction "C_K") (pintype "passive"))
      (node (ref "T3P2") (pin "K") (pinfunction "C_K") (pintype "passive"))
      (node (ref "T4P2") (pin "K") (pinfunction "C_K") (pintype "passive"))
    )
    (net (code "36") (name "Net-(CK3-C)") (class "Default")
      (node (ref "CK3") (pin "K") (pinfunction "C_K") (pintype "passive"))
      (node (ref "MAX7219") (pin "7") (pinfunction "DIG3_7") (pintype "output"))
      (node (ref "T1P3") (pin "K") (pinfunction "C_K") (pintype "passive"))
      (node (ref "T2B") (pin "K") (pinfunction "C_K") (pintype "passive"))
      (node (ref "T2P3") (pin "K") (pinfunction "C_K") (pintype "passive"))
      (node (ref "T3P3") (pin "K") (pinfunction "C_K") (pintype "passive"))
      (node (ref "T4P3") (pin "K") (pinfunction "C_K") (pintype "passive"))
    )
    (net (code "37") (name "Net-(CK4-C)") (class "Default")
      (node (ref "CK4") (pin "K") (pinfunction "C_K") (pintype "passive"))
      (node (ref "MAX7219") (pin "6") (pinfunction "DIG2_6") (pintype "output"))
      (node (ref "T1P4") (pin "K") (pinfunction "C_K") (pintype "passive"))
      (node (ref "T2P4") (pin "K") (pinfunction "C_K") (pintype "passive"))
      (node (ref "T3P4") (pin "K") (pinfunction "C_K") (pintype "passive"))
      (node (ref "T3R") (pin "K") (pinfunction "C_K") (pintype "passive"))
      (node (ref "T4P4") (pin "K") (pinfunction "C_K") (pintype "passive"))
    )
    (net (code "38") (name "Net-(CK5-C)") (class "Default")
      (node (ref "CK5") (pin "K") (pinfunction "C_K") (pintype "passive"))
      (node (ref "MAX7219") (pin "5") (pinfunction "DIG6_5") (pintype "output"))
      (node (ref "T1P5") (pin "K") (pinfunction "C_K") (pintype "passive"))
      (node (ref "T2P5") (pin "K") (pinfunction "C_K") (pintype "passive"))
      (node (ref "T3B") (pin "K") (pinfunction "C_K") (pintype "passive"))
      (node (ref "T3P5") (pin "K") (pinfunction "C_K") (pintype "passive"))
      (node (ref "T4P5") (pin "K") (pinfunction "C_K") (pintype "passive"))
    )
    (net (code "39") (name "Net-(CK6-C)") (class "Default")
      (node (ref "CK6") (pin "K") (pinfunction "C_K") (pintype "passive"))
      (node (ref "MAX7219") (pin "3") (pinfunction "DIG4_3") (pintype "output"))
      (node (ref "T1P6") (pin "K") (pinfunction "C_K") (pintype "passive"))
      (node (ref "T2P6") (pin "K") (pinfunction "C_K") (pintype "passive"))
      (node (ref "T3P6") (pin "K") (pinfunction "C_K") (pintype "passive"))
      (node (ref "T4P6") (pin "K") (pinfunction "C_K") (pintype "passive"))
      (node (ref "T4R") (pin "K") (pinfunction "C_K") (pintype "passive"))
    )
    (net (code "40") (name "Net-(CK7-C)") (class "Default")
      (node (ref "CK7") (pin "K") (pinfunction "C_K") (pintype "passive"))
      (node (ref "MAX7219") (pin "2") (pinfunction "DIG0_2") (pintype "output"))
      (node (ref "T1P7") (pin "K") (pinfunction "C_K") (pintype "passive"))
      (node (ref "T2P7") (pin "K") (pinfunction "C_K") (pintype "passive"))
      (node (ref "T3P7") (pin "K") (pinfunction "C_K") (pintype "passive"))
      (node (ref "T4B") (pin "K") (pinfunction "C_K") (pintype "passive"))
      (node (ref "T4P7") (pin "K") (pinfunction "C_K") (pintype "passive"))
    )
    (net (code "41") (name "Net-(CLKIN-Pad2)") (class "Default")
      (node (ref "CLKIN") (pin "2") (pinfunction "2_2") (pintype "passive"))
      (node (ref "CLKIN") (pin "4") (pinfunction "4_4") (pintype "passive"))
      (node (ref "CLKSEL") (pin "1") (pinfunction "1_1") (pintype "passive"))
    )
    (net (code "42") (name "Net-(CLKLED-C)") (class "Default")
      (node (ref "CLKLED") (pin "K") (pinfunction "C_K") (pintype "passive"))
      (node (ref "R3") (pin "2") (pinfunction "2_2") (pintype "passive"))
    )
    (net (code "43") (name "Net-(CLKLED-PadA)") (class "Default")
      (node (ref "CLKLED") (pin "A") (pinfunction "A_A") (pintype "passive"))
      (node (ref "CLKSEL") (pin "2") (pinfunction "2_2") (pintype "passive"))
      (node (ref "PCB1") (pin "A2") (pinfunction "A2_A2") (pintype "bidirectional"))
    )
    (net (code "44") (name "Net-(CLKOUT-Pad2)") (class "Default")
      (node (ref "CLKOUT") (pin "2") (pinfunction "2_2") (pintype "passive"))
      (node (ref "CLKOUT") (pin "4") (pinfunction "4_4") (pintype "passive"))
      (node (ref "CLKSEL") (pin "3") (pinfunction "3_3") (pintype "passive"))
      (node (ref "PCB1") (pin "A3") (pinfunction "A3_A3") (pintype "bidirectional"))
    )
    (net (code "45") (name "Net-(CONTRA-S)") (class "Default")
      (node (ref "CONTRA") (pin "1") (pinfunction "S_1") (pintype "passive"))
      (node (ref "R15") (pin "2") (pinfunction "2_2") (pintype "passive"))
    )
    (net (code "46") (name "Net-(J1-Pad1)") (class "Default")
      (node (ref "J1") (pin "1") (pinfunction "1_1") (pintype "passive"))
      (node (ref "ONOFFSW") (pin "2") (pinfunction "2_2") (pintype "passive"))
    )
    (net (code "47") (name "Net-(MAX7219-CLK)") (class "Default")
      (node (ref "8CONCNTRL") (pin "3") (pinfunction "3_3") (pintype "passive"))
      (node (ref "8CONMATRIZ") (pin "3") (pinfunction "3_3") (pintype "passive"))
      (node (ref "MAX7219") (pin "13") (pinfunction "CLK_13") (pintype "input"))
      (node (ref "PCB1") (pin "D5") (pinfunction "D5_D5") (pintype "bidirectional"))
    )
    (net (code "48") (name "Net-(MAX7219-DIN)") (class "Default")
      (node (ref "8CONCNTRL") (pin "4") (pinfunction "4_4") (pintype "passive"))
      (node (ref "8CONMATRIZ") (pin "4") (pinfunction "4_4") (pintype "passive"))
      (node (ref "MAX7219") (pin "1") (pinfunction "DIN_1") (pintype "input"))
      (node (ref "PCB1") (pin "D6") (pinfunction "D6_D6") (pintype "bidirectional"))
    )
    (net (code "49") (name "Net-(MAX7219-ISET)") (class "Default")
      (node (ref "MAX7219") (pin "18") (pinfunction "ISET_18") (pintype "input"))
      (node (ref "R20") (pin "1") (pinfunction "1_1") (pintype "passive"))
    )
    (net (code "50") (name "Net-(MAX7219-LOAD)") (class "Default")
      (node (ref "8CONCNTRL") (pin "2") (pinfunction "2_2") (pintype "passive"))
      (node (ref "8CONMATRIZ") (pin "2") (pinfunction "2_2") (pintype "passive"))
      (node (ref "MAX7219") (pin "12") (pinfunction "LOAD_12") (pintype "input"))
      (node (ref "PCB1") (pin "D4") (pinfunction "D4_D4") (pintype "bidirectional"))
    )
    (net (code "51") (name "Net-(MAX7219-SEGC)") (class "Default")
      (node (ref "MAX7219") (pin "20") (pinfunction "SEGC_20") (pintype "output"))
      (node (ref "T2P0") (pin "A") (pinfunction "A_A") (pintype "passive"))
      (node (ref "T2P1") (pin "A") (pinfunction "A_A") (pintype "passive"))
      (node (ref "T2P2") (pin "A") (pinfunction "A_A") (pintype "passive"))
      (node (ref "T2P3") (pin "A") (pinfunction "A_A") (pintype "passive"))
      (node (ref "T2P4") (pin "A") (pinfunction "A_A") (pintype "passive"))
      (node (ref "T2P5") (pin "A") (pinfunction "A_A") (pintype "passive"))
      (node (ref "T2P6") (pin "A") (pinfunction "A_A") (pintype "passive"))
      (node (ref "T2P7") (pin "A") (pinfunction "A_A") (pintype "passive"))
    )
    (net (code "52") (name "Net-(MAX7219-SEGD)") (class "Default")
      (node (ref "CK0") (pin "A") (pinfunction "A_A") (pintype "passive"))
      (node (ref "CK1") (pin "A") (pinfunction "A_A") (pintype "passive"))
      (node (ref "CK2") (pin "A") (pinfunction "A_A") (pintype "passive"))
      (node (ref "CK3") (pin "A") (pinfunction "A_A") (pintype "passive"))
      (node (ref "CK4") (pin "A") (pinfunction "A_A") (pintype "passive"))
      (node (ref "CK5") (pin "A") (pinfunction "A_A") (pintype "passive"))
      (node (ref "CK6") (pin "A") (pinfunction "A_A") (pintype "passive"))
      (node (ref "CK7") (pin "A") (pinfunction "A_A") (pintype "passive"))
      (node (ref "MAX7219") (pin "23") (pinfunction "SEGD_23") (pintype "output"))
    )
    (net (code "53") (name "Net-(MAX7219-SEGDP)") (class "Default")
      (node (ref "MAX7219") (pin "22") (pinfunction "SEGDP_22") (pintype "output"))
      (node (ref "T4P0") (pin "A") (pinfunction "A_A") (pintype "passive"))
      (node (ref "T4P1") (pin "A") (pinfunction "A_A") (pintype "passive"))
      (node (ref "T4P2") (pin "A") (pinfunction "A_A") (pintype "passive"))
      (node (ref "T4P3") (pin "A") (pinfunction "A_A") (pintype "passive"))
      (node (ref "T4P4") (pin "A") (pinfunction "A_A") (pintype "passive"))
      (node (ref "T4P5") (pin "A") (pinfunction "A_A") (pintype "passive"))
      (node (ref "T4P6") (pin "A") (pinfunction "A_A") (pintype "passive"))
      (node (ref "T4P7") (pin "A") (pinfunction "A_A") (pintype "passive"))
    )
    (net (code "54") (name "Net-(MAX7219-SEGE)") (class "Default")
      (node (ref "MAX7219") (pin "21") (pinfunction "SEGE_21") (pintype "output"))
      (node (ref "T3P0") (pin "A") (pinfunction "A_A") (pintype "passive"))
      (node (ref "T3P1") (pin "A") (pinfunction "A_A") (pintype "passive"))
      (node (ref "T3P2") (pin "A") (pinfunction "A_A") (pintype "passive"))
      (node (ref "T3P3") (pin "A") (pinfunction "A_A") (pintype "passive"))
      (node (ref "T3P4") (pin "A") (pinfunction "A_A") (pintype "passive"))
      (node (ref "T3P5") (pin "A") (pinfunction "A_A") (pintype "passive"))
      (node (ref "T3P6") (pin "A") (pinfunction "A_A") (pintype "passive"))
      (node (ref "T3P7") (pin "A") (pinfunction "A_A") (pintype "passive"))
    )
    (net (code "55") (name "Net-(MAX7219-SEGF)") (class "Default")
      (node (ref "MAX7219") (pin "15") (pinfunction "SEGF_15") (pintype "output"))
      (node (ref "T1B") (pin "A") (pinfunction "A_A") (pintype "passive"))
      (node (ref "T1R") (pin "A") (pinfunction "A_A") (pintype "passive"))
      (node (ref "T2B") (pin "A") (pinfunction "A_A") (pintype "passive"))
      (node (ref "T2R") (pin "A") (pinfunction "A_A") (pintype "passive"))
      (node (ref "T3B") (pin "A") (pinfunction "A_A") (pintype "passive"))
      (node (ref "T3R") (pin "A") (pinfunction "A_A") (pintype "passive"))
      (node (ref "T4B") (pin "A") (pinfunction "A_A") (pintype "passive"))
      (node (ref "T4R") (pin "A") (pinfunction "A_A") (pintype "passive"))
    )
    (net (code "56") (name "Net-(MAX7219-SEGG)") (class "Default")
      (node (ref "MAX7219") (pin "17") (pinfunction "SEGG_17") (pintype "output"))
      (node (ref "T1P0") (pin "A") (pinfunction "A_A") (pintype "passive"))
      (node (ref "T1P1") (pin "A") (pinfunction "A_A") (pintype "passive"))
      (node (ref "T1P2") (pin "A") (pinfunction "A_A") (pintype "passive"))
      (node (ref "T1P3") (pin "A") (pinfunction "A_A") (pintype "passive"))
      (node (ref "T1P4") (pin "A") (pinfunction "A_A") (pintype "passive"))
      (node (ref "T1P5") (pin "A") (pinfunction "A_A") (pintype "passive"))
      (node (ref "T1P6") (pin "A") (pinfunction "A_A") (pintype "passive"))
      (node (ref "T1P7") (pin "A") (pinfunction "A_A") (pintype "passive"))
    )
    (net (code "57") (name "Net-(P12-Pad1)") (class "Default")
      (node (ref "P12") (pin "1") (pinfunction "1_1") (pintype "passive"))
      (node (ref "PCB1") (pin "D12") (pinfunction "D12_D12") (pintype "bidirectional"))
    )
    (net (code "58") (name "Net-(P13-Pad1)") (class "Default")
      (node (ref "P13") (pin "1") (pinfunction "1_1") (pintype "passive"))
      (node (ref "PCB1") (pin "D13") (pinfunction "D13_D13") (pintype "bidirectional"))
    )
    (net (code "59") (name "Net-(PCB1-PadA0)") (class "Default")
      (node (ref "PCB1") (pin "A0") (pinfunction "A0_A0") (pintype "bidirectional"))
      (node (ref "R2") (pin "1") (pinfunction "1_1") (pintype "passive"))
    )
    (net (code "60") (name "Net-(PCB1-PadA1)") (class "Default")
      (node (ref "PCB1") (pin "A1") (pinfunction "A1_A1") (pintype "bidirectional"))
      (node (ref "R1") (pin "1") (pinfunction "1_1") (pintype "passive"))
    )
    (net (code "61") (name "Net-(PCB1-PadTX1)") (class "Default")
      (node (ref "PCB1") (pin "TX1") (pinfunction "TX1_TX1") (pintype "bidirectional"))
      (node (ref "TXRX") (pin "3") (pinfunction "3_3") (pintype "passive"))
    )
    (net (code "62") (name "Net-(PCB1-RX0)") (class "Default")
      (node (ref "PCB1") (pin "RX1") (pinfunction "RX0_RX1") (pintype "bidirectional"))
      (node (ref "TXRX") (pin "2") (pinfunction "2_2") (pintype "passive"))
    )
    (net (code "63") (name "Net-(PLAY-S)") (class "Default")
      (node (ref "PLAY") (pin "1") (pinfunction "S_1") (pintype "passive"))
      (node (ref "R14") (pin "2") (pinfunction "2_2") (pintype "passive"))
    )
    (net (code "64") (name "Net-(POSITION-Pad2)") (class "Default")
      (node (ref "POSITION") (pin "2") (pinfunction "2_2") (pintype "passive"))
      (node (ref "R1") (pin "2") (pinfunction "2_2") (pintype "passive"))
    )
    (net (code "65") (name "Net-(R2-Pad2)") (class "Default")
      (node (ref "R2") (pin "2") (pinfunction "2_2") (pintype "passive"))
      (node (ref "TEMPOT") (pin "2") (pinfunction "2_2") (pintype "passive"))
    )
    (net (code "66") (name "Net-(ST0-S1)") (class "Default")
      (node (ref "R4") (pin "2") (pinfunction "2_2") (pintype "passive"))
      (node (ref "ST0") (pin "2") (pinfunction "S1_2") (pintype "passive"))
    )
    (net (code "67") (name "Net-(ST1-S1)") (class "Default")
      (node (ref "R5") (pin "2") (pinfunction "2_2") (pintype "passive"))
      (node (ref "ST1") (pin "2") (pinfunction "S1_2") (pintype "passive"))
    )
    (net (code "68") (name "Net-(ST2-S1)") (class "Default")
      (node (ref "R6") (pin "2") (pinfunction "2_2") (pintype "passive"))
      (node (ref "ST2") (pin "2") (pinfunction "S1_2") (pintype "passive"))
    )
    (net (code "69") (name "Net-(ST3-S1)") (class "Default")
      (node (ref "R7") (pin "2") (pinfunction "2_2") (pintype "passive"))
      (node (ref "ST3") (pin "2") (pinfunction "S1_2") (pintype "passive"))
    )
    (net (code "70") (name "Net-(ST4-S1)") (class "Default")
      (node (ref "R8") (pin "2") (pinfunction "2_2") (pintype "passive"))
      (node (ref "ST4") (pin "2") (pinfunction "S1_2") (pintype "passive"))
    )
    (net (code "71") (name "Net-(ST5-S1)") (class "Default")
      (node (ref "R9") (pin "2") (pinfunction "2_2") (pintype "passive"))
      (node (ref "ST5") (pin "2") (pinfunction "S1_2") (pintype "passive"))
    )
    (net (code "72") (name "Net-(ST6-S1)") (class "Default")
      (node (ref "R10") (pin "2") (pinfunction "2_2") (pintype "passive"))
      (node (ref "ST6") (pin "2") (pinfunction "S1_2") (pintype "passive"))
    )
    (net (code "73") (name "Net-(ST7-S1)") (class "Default")
      (node (ref "R11") (pin "2") (pinfunction "2_2") (pintype "passive"))
      (node (ref "ST7") (pin "2") (pinfunction "S1_2") (pintype "passive"))
    )
    (net (code "74") (name "Net-(TR1-S)") (class "Default")
      (node (ref "R17") (pin "2") (pinfunction "2_2") (pintype "passive"))
      (node (ref "TR1") (pin "1") (pinfunction "S_1") (pintype "passive"))
    )
    (net (code "75") (name "Net-(TR2-S)") (class "Default")
      (node (ref "R16") (pin "2") (pinfunction "2_2") (pintype "passive"))
      (node (ref "TR2") (pin "1") (pinfunction "S_1") (pintype "passive"))
    )
    (net (code "76") (name "Net-(TR3-S)") (class "Default")
      (node (ref "R12") (pin "2") (pinfunction "2_2") (pintype "passive"))
      (node (ref "TR3") (pin "1") (pinfunction "S_1") (pintype "passive"))
    )
    (net (code "77") (name "Net-(TR4-S)") (class "Default")
      (node (ref "R13") (pin "2") (pinfunction "2_2") (pintype "passive"))
      (node (ref "TR4") (pin "1") (pinfunction "S_1") (pintype "passive"))
    )
    (net (code "78") (name "VDD") (class "Default")
      (node (ref "8CONCNTRL") (pin "1") (pinfunction "1_1") (pintype "passive"))
      (node (ref "8CONMATRIZ") (pin "1") (pinfunction "1_1") (pintype "passive"))
      (node (ref "ACTIVE") (pin "3") (pinfunction "P_3") (pintype "passive"))
      (node (ref "ACTIVE") (pin "4") (pinfunction "P1_4") (pintype "passive"))
      (node (ref "C13") (pin "+") (pinfunction "+_+") (pintype "passive"))
      (node (ref "C14") (pin "1") (pinfunction "1_1") (pintype "passive"))
      (node (ref "C7") (pin "+") (pinfunction "+_+") (pintype "passive"))
      (node (ref "CONTRA") (pin "3") (pinfunction "P_3") (pintype "passive"))
      (node (ref "CONTRA") (pin "4") (pinfunction "P1_4") (pintype "passive"))
      (node (ref "IC1") (pin "3") (pinfunction "VO_3") (pintype "passive"))
      (node (ref "MAX7219") (pin "19") (pinfunction "VCC_19") (pintype "power_in"))
      (node (ref "PLAY") (pin "3") (pinfunction "P_3") (pintype "passive"))
      (node (ref "PLAY") (pin "4") (pinfunction "P1_4") (pintype "passive"))
      (node (ref "POSITION") (pin "1") (pinfunction "1_1") (pintype "passive"))
      (node (ref "R20") (pin "2") (pinfunction "2_2") (pintype "passive"))
      (node (ref "ST0") (pin "3") (pinfunction "P_3") (pintype "passive"))
      (node (ref "ST0") (pin "4") (pinfunction "P1_4") (pintype "passive"))
      (node (ref "ST1") (pin "3") (pinfunction "P_3") (pintype "passive"))
      (node (ref "ST1") (pin "4") (pinfunction "P1_4") (pintype "passive"))
      (node (ref "ST2") (pin "3") (pinfunction "P_3") (pintype "passive"))
      (node (ref "ST2") (pin "4") (pinfunction "P1_4") (pintype "passive"))
      (node (ref "ST3") (pin "3") (pinfunction "P_3") (pintype "passive"))
      (node (ref "ST3") (pin "4") (pinfunction "P1_4") (pintype "passive"))
      (node (ref "ST4") (pin "3") (pinfunction "P_3") (pintype "passive"))
      (node (ref "ST4") (pin "4") (pinfunction "P1_4") (pintype "passive"))
      (node (ref "ST5") (pin "3") (pinfunction "P_3") (pintype "passive"))
      (node (ref "ST5") (pin "4") (pinfunction "P1_4") (pintype "passive"))
      (node (ref "ST6") (pin "3") (pinfunction "P_3") (pintype "passive"))
      (node (ref "ST6") (pin "4") (pinfunction "P1_4") (pintype "passive"))
      (node (ref "ST7") (pin "3") (pinfunction "P_3") (pintype "passive"))
      (node (ref "ST7") (pin "4") (pinfunction "P1_4") (pintype "passive"))
      (node (ref "TEMPOT") (pin "1") (pinfunction "1_1") (pintype "passive"))
      (node (ref "TR1") (pin "3") (pinfunction "P_3") (pintype "passive"))
      (node (ref "TR1") (pin "4") (pinfunction "P1_4") (pintype "passive"))
      (node (ref "TR2") (pin "3") (pinfunction "P_3") (pintype "passive"))
      (node (ref "TR2") (pin "4") (pinfunction "P1_4") (pintype "passive"))
      (node (ref "TR3") (pin "3") (pinfunction "P_3") (pintype "passive"))
      (node (ref "TR3") (pin "4") (pinfunction "P1_4") (pintype "passive"))
      (node (ref "TR4") (pin "3") (pinfunction "P_3") (pintype "passive"))
      (node (ref "TR4") (pin "4") (pinfunction "P1_4") (pintype "passive"))
      (node (ref "VDD") (pin "1") (pinfunction "1_1") (pintype "passive"))
      (node (ref "VDD") (pin "2") (pinfunction "2_2") (pintype "passive"))
      (node (ref "VDD") (pin "3") (pinfunction "3_3") (pintype "passive"))
      (node (ref "VDD") (pin "4") (pinfunction "4_4") (pintype "passive"))
    )
    (net (code "79") (name "unconnected-(4021CNTRLA-Q6-Pad2)") (class "Default")
      (node (ref "4021CNTRL") (pin "2") (pinfunction "Q6_2") (pintype "output"))
    )
    (net (code "80") (name "unconnected-(4021CNTRLA-Q7-Pad12)") (class "Default")
      (node (ref "4021CNTRL") (pin "12") (pinfunction "Q7_12") (pintype "output"))
    )
    (net (code "81") (name "unconnected-(4021CNTRLA-SI-Pad11)") (class "Default")
      (node (ref "4021CNTRL") (pin "11") (pinfunction "SI_11") (pintype "input"))
    )
    (net (code "82") (name "unconnected-(4021STEPSA-Q6-Pad2)") (class "Default")
      (node (ref "4021STEPS") (pin "2") (pinfunction "Q6_2") (pintype "output"))
    )
    (net (code "83") (name "unconnected-(4021STEPSA-Q7-Pad12)") (class "Default")
      (node (ref "4021STEPS") (pin "12") (pinfunction "Q7_12") (pintype "output"))
    )
    (net (code "84") (name "unconnected-(MAX7219-DOUT-Pad24)") (class "Default")
      (node (ref "MAX7219") (pin "24") (pinfunction "DOUT_24") (pintype "output"))
    )
    (net (code "85") (name "unconnected-(MAX7219-SEGA-Pad14)") (class "Default")
      (node (ref "MAX7219") (pin "14") (pinfunction "SEGA_14") (pintype "output"))
    )
    (net (code "86") (name "unconnected-(MAX7219-SEGB-Pad16)") (class "Default")
      (node (ref "MAX7219") (pin "16") (pinfunction "SEGB_16") (pintype "output"))
    )
    (net (code "87") (name "unconnected-(PCB1-Pad3V3)") (class "Default")
      (node (ref "PCB1") (pin "3V3") (pinfunction "3V3_3V3") (pintype "bidirectional"))
    )
    (net (code "88") (name "unconnected-(PCB1-Pad5V)") (class "Default")
      (node (ref "PCB1") (pin "5V") (pinfunction "5V_5V") (pintype "bidirectional"))
    )
    (net (code "89") (name "unconnected-(PCB1-PadREF)") (class "Default")
      (node (ref "PCB1") (pin "REF") (pinfunction "REF_REF") (pintype "bidirectional"))
    )
    (net (code "90") (name "unconnected-(PCB1-PadRST)") (class "Default")
      (node (ref "PCB1") (pin "RST") (pinfunction "RST_RST") (pintype "bidirectional"))
    )
    (net (code "91") (name "unconnected-(PCB1-PadRST.)") (class "Default")
      (node (ref "PCB1") (pin "RST.") (pinfunction "RST._RST.") (pintype "bidirectional"))
    )
  )
)
